# GRLV_DoubleRail_Part1_V0_1.net
KiCad netlist of a schematic drawn in Altium Designer
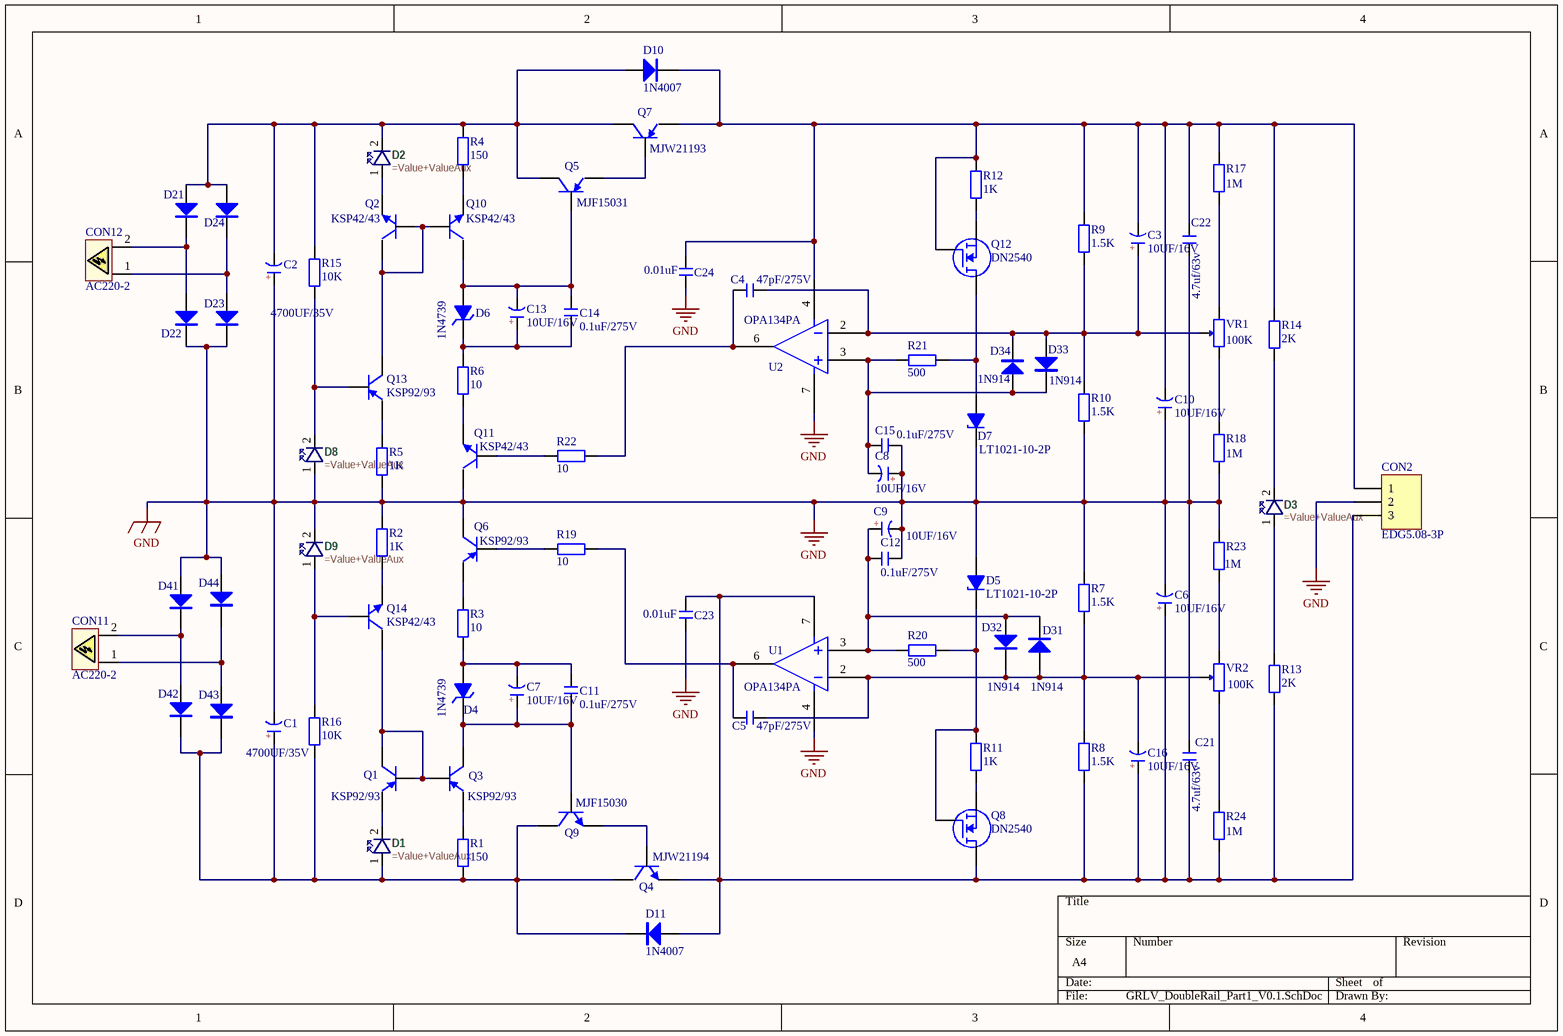
[diagram p0: GRLV_DoubleRail_Part1_V0.1.SchDoc]

(export (version "E")
  (design (tool "Eeschema 10.0.6"))
  (components
    (comp (ref "C1")
      (value "4700UF/35V")
      (footprint "CAP 11*35*60")
      (description "直插电解电容")
      (fields (field (name "版权归属") "源创客"))
      (libsource (lib "") (part "C-CAP_1"))
    )
    (comp (ref "C2")
      (value "4700UF/35V")
      (footprint "CAP 11*35*60")
      (description "直插电解电容")
      (fields (field (name "版权归属") "源创客"))
      (libsource (lib "") (part "C-CAP_1"))
    )
    (comp (ref "C3")
      (value "10UF/16V")
      (footprint "CAP 1.5*4*8")
      (description "直插电解电容")
      (fields (field (name "版权归属") "源创客"))
      (libsource (lib "") (part "C-CAP_1"))
    )
    (comp (ref "C4")
      (value "47pF/275V")
      (footprint "CBB 6.3*6.3*5")
      (description "CBB电容")
      (fields (field (name "版权归属") "源创客"))
      (libsource (lib "电阻-电容-电感") (part "C-CBB"))
    )
    (comp (ref "C5")
      (value "47pF/275V")
      (footprint "CBB 6.3*6.3*5")
      (description "CBB电容")
      (fields (field (name "版权归属") "源创客"))
      (libsource (lib "电阻-电容-电感") (part "C-CBB"))
    )
    (comp (ref "C6")
      (value "10UF/16V")
      (footprint "CAP 3.5*8*11.5")
      (description "直插电解电容")
      (fields (field (name "版权归属") "源创客"))
      (libsource (lib "") (part "C-CAP_1"))
    )
    (comp (ref "C7")
      (value "10UF/16V")
      (footprint "CAP 1.5*4*8")
      (description "直插电解电容")
      (fields (field (name "版权归属") "源创客"))
      (libsource (lib "") (part "C-CAP_1"))
    )
    (comp (ref "C8")
      (value "10UF/16V")
      (footprint "CAP 1.5*4*8")
      (description "直插电解电容")
      (fields (field (name "版权归属") "源创客"))
      (libsource (lib "电阻-电容-电感") (part "C-CAP"))
    )
    (comp (ref "C9")
      (value "10UF/16V")
      (footprint "CAP 1.5*4*8")
      (description "直插电解电容")
      (fields (field (name "版权归属") "源创客"))
      (libsource (lib "电阻-电容-电感") (part "C-CAP"))
    )
    (comp (ref "C10")
      (value "10UF/16V")
      (footprint "CAP 3.5*8*11.5")
      (description "直插电解电容")
      (fields (field (name "版权归属") "源创客"))
      (libsource (lib "") (part "C-CAP_1"))
    )
    (comp (ref "C11")
      (value "0.1uF/275V")
      (footprint "CBB 6.3*6.3*5")
      (description "CBB电容")
      (fields (field (name "版权归属") "源创客"))
      (libsource (lib "电阻-电容-电感") (part "C-CBB"))
    )
    (comp (ref "C12")
      (value "0.1uF/275V")
      (footprint "CBB 6.3*6.3*5")
      (description "CBB电容")
      (fields (field (name "版权归属") "源创客"))
      (libsource (lib "电阻-电容-电感") (part "C-CBB"))
    )
    (comp (ref "C13")
      (value "10UF/16V")
      (footprint "CAP 1.5*4*8")
      (description "直插电解电容")
      (fields (field (name "版权归属") "源创客"))
      (libsource (lib "") (part "C-CAP_1"))
    )
    (comp (ref "C14")
      (value "0.1uF/275V")
      (footprint "CBB 6.3*6.3*5")
      (description "CBB电容")
      (fields (field (name "版权归属") "源创客"))
      (libsource (lib "电阻-电容-电感") (part "C-CBB"))
    )
    (comp (ref "C15")
      (value "0.1uF/275V")
      (footprint "CBB 6.3*6.3*5")
      (description "CBB电容")
      (fields (field (name "版权归属") "源创客"))
      (libsource (lib "电阻-电容-电感") (part "C-CBB"))
    )
    (comp (ref "C16")
      (value "10UF/16V")
      (footprint "CAP 1.5*4*8")
      (description "直插电解电容")
      (fields (field (name "版权归属") "源创客"))
      (libsource (lib "") (part "C-CAP_1"))
    )
    (comp (ref "C21")
      (value "4.7uf/63v")
      (footprint "CBB 7.2*7.2*13")
      (description "MKS薄膜电容")
      (libsource (lib "电阻-电容-电感") (part "C-MKS"))
    )
    (comp (ref "C22")
      (value "4.7uf/63v")
      (footprint "CBB 7.2*7.2*13")
      (description "MKS薄膜电容")
      (libsource (lib "电阻-电容-电感") (part "C-MKS"))
    )
    (comp (ref "C23")
      (value "0.01uF")
      (footprint "CBB 6.3*6.3*5")
      (description "CBB电容")
      (fields (field (name "Comment") "0.01uF/275V") (field (name "版权归属") "源创客"))
      (libsource (lib "电阻-电容-电感") (part "C-CBB"))
    )
    (comp (ref "C24")
      (value "0.01uF")
      (footprint "CBB 6.3*6.3*5")
      (description "CBB电容")
      (fields (field (name "Comment") "0.01uF/275V") (field (name "版权归属") "源创客"))
      (libsource (lib "电阻-电容-电感") (part "C-CBB"))
    )
    (comp (ref "CON2")
      (value "EDG5.08-3P")
      (footprint "HX5.08-3S")
      (libsource (lib "Connectors") (part "EDG5.08-3P"))
    )
    (comp (ref "CON11")
      (value "AC220-2")
      (footprint "HX5.08-2S")
      (libsource (lib "Connectors") (part "AC220-2"))
    )
    (comp (ref "CON12")
      (value "AC220-2")
      (footprint "HX5.08-2S")
      (libsource (lib "Connectors") (part "AC220-2"))
    )
    (comp (ref "D1")
      (value "~")
      (footprint "LED 3MM-R")
      (description "直插式LED")
      (libsource (lib "LED") (part "LED"))
    )
    (comp (ref "D2")
      (value "~")
      (footprint "LED 3MM-R")
      (description "直插式LED")
      (libsource (lib "LED") (part "LED"))
    )
    (comp (ref "D3")
      (value "~")
      (footprint "LED 3MM-R")
      (description "直插式LED")
      (libsource (lib "LED") (part "LED"))
    )
    (comp (ref "D4")
      (value "1N4739")
      (footprint "DO-41")
      (description "9.1V/1W稳压管")
      (libsource (lib "二极管-整流桥") (part "1N4739"))
    )
    (comp (ref "D5")
      (value "LT1021-10-2P")
      (footprint "DIP8-300_MH")
      (description "10V Precision Reference 2 Pin Config")
      (libsource (lib "电压参考") (part "LT1021-10-2P"))
    )
    (comp (ref "D6")
      (value "1N4739")
      (footprint "DO-41")
      (description "9.1V/1W稳压管")
      (libsource (lib "二极管-整流桥") (part "1N4739"))
    )
    (comp (ref "D7")
      (value "LT1021-10-2P")
      (footprint "DIP8-300_MH")
      (description "10V Precision Reference 2 Pin Config")
      (libsource (lib "电压参考") (part "LT1021-10-2P"))
    )
    (comp (ref "D8")
      (value "~")
      (footprint "LED 3MM-R")
      (description "直插式LED")
      (libsource (lib "LED") (part "LED"))
    )
    (comp (ref "D9")
      (value "~")
      (footprint "LED 3MM-R")
      (description "直插式LED")
      (libsource (lib "LED") (part "LED"))
    )
    (comp (ref "D10")
      (value "1N4007")
      (footprint "DO-41")
      (description "整流二极管")
      (fields (field (name "版权归属") "源创客"))
      (libsource (lib "二极管-整流桥") (part "1N4007"))
    )
    (comp (ref "D11")
      (value "1N4007")
      (footprint "DO-41")
      (description "整流二极管")
      (fields (field (name "版权归属") "源创客"))
      (libsource (lib "二极管-整流桥") (part "1N4007"))
    )
    (comp (ref "D21")
      (value "VS-HFA08TB60-M3")
      (footprint "TO220AC")
      (description "Ultrafast Soft Recovery Diado 8A 600V")
      (libsource (lib "二极管-整流桥") (part "VS-HFA08TB60-M3"))
    )
    (comp (ref "D22")
      (value "VS-HFA08TB60-M3")
      (footprint "TO220AC")
      (description "Ultrafast Soft Recovery Diado 8A 600V")
      (libsource (lib "二极管-整流桥") (part "VS-HFA08TB60-M3"))
    )
    (comp (ref "D23")
      (value "VS-HFA08TB60-M3")
      (footprint "TO220AC")
      (description "Ultrafast Soft Recovery Diado 8A 600V")
      (libsource (lib "二极管-整流桥") (part "VS-HFA08TB60-M3"))
    )
    (comp (ref "D24")
      (value "VS-HFA08TB60-M3")
      (footprint "TO220AC")
      (description "Ultrafast Soft Recovery Diado 8A 600V")
      (libsource (lib "二极管-整流桥") (part "VS-HFA08TB60-M3"))
    )
    (comp (ref "D31")
      (value "1N914")
      (footprint "DO-35")
      (description "高速开关管 1V/0.25W")
      (libsource (lib "二极管-整流桥") (part "1N914"))
    )
    (comp (ref "D32")
      (value "1N914")
      (footprint "DO-35")
      (description "高速开关管 1V/0.25W")
      (libsource (lib "二极管-整流桥") (part "1N914"))
    )
    (comp (ref "D33")
      (value "1N914")
      (footprint "DO-35")
      (description "高速开关管 1V/0.25W")
      (libsource (lib "二极管-整流桥") (part "1N914"))
    )
    (comp (ref "D34")
      (value "1N914")
      (footprint "DO-35")
      (description "高速开关管 1V/0.25W")
      (libsource (lib "二极管-整流桥") (part "1N914"))
    )
    (comp (ref "D41")
      (value "VS-HFA08TB60-M3")
      (footprint "TO220AC")
      (description "Ultrafast Soft Recovery Diado 8A 600V")
      (libsource (lib "二极管-整流桥") (part "VS-HFA08TB60-M3"))
    )
    (comp (ref "D42")
      (value "VS-HFA08TB60-M3")
      (footprint "TO220AC")
      (description "Ultrafast Soft Recovery Diado 8A 600V")
      (libsource (lib "二极管-整流桥") (part "VS-HFA08TB60-M3"))
    )
    (comp (ref "D43")
      (value "VS-HFA08TB60-M3")
      (footprint "TO220AC")
      (description "Ultrafast Soft Recovery Diado 8A 600V")
      (libsource (lib "二极管-整流桥") (part "VS-HFA08TB60-M3"))
    )
    (comp (ref "D44")
      (value "VS-HFA08TB60-M3")
      (footprint "TO220AC")
      (description "Ultrafast Soft Recovery Diado 8A 600V")
      (libsource (lib "二极管-整流桥") (part "VS-HFA08TB60-M3"))
    )
    (comp (ref "Q1")
      (value "KSP92/93")
      (footprint "TO92A")
      (description "High Voltage PNP Transistor")
      (libsource (lib "三极管") (part "KSP92/93"))
    )
    (comp (ref "Q2")
      (value "KSP42/43")
      (footprint "TO92A")
      (description "High Voltage NPN Transistor")
      (libsource (lib "三极管") (part "KSP42/43"))
    )
    (comp (ref "Q3")
      (value "KSP92/93")
      (footprint "TO92A")
      (description "High Voltage PNP Transistor")
      (libsource (lib "三极管") (part "KSP92/93"))
    )
    (comp (ref "Q4")
      (value "MJW21194")
      (footprint "TO247V")
      (description "Power NPN Transistor")
      (libsource (lib "三极管") (part "MJW21194"))
    )
    (comp (ref "Q5")
      (value "MJF15031")
      (footprint "TO220V")
      (description "Power PNP Transistor")
      (libsource (lib "三极管") (part "MJF15031"))
    )
    (comp (ref "Q6")
      (value "KSP92/93")
      (footprint "TO92A")
      (description "High Voltage PNP Transistor")
      (libsource (lib "三极管") (part "KSP92/93"))
    )
    (comp (ref "Q7")
      (value "MJW21193")
      (footprint "TO247V")
      (description "Power PNP Transistor")
      (libsource (lib "三极管") (part "MJW21193"))
    )
    (comp (ref "Q8")
      (value "DN2540")
      (footprint "TO92A")
      (description "N沟道耗尽型DMOS场效应管 400V/150ma")
      (libsource (lib "场效应管") (part "DN2540"))
    )
    (comp (ref "Q9")
      (value "MJF15030")
      (footprint "TO220V")
      (description "Power NPN Transistor")
      (libsource (lib "三极管") (part "MJF15030"))
    )
    (comp (ref "Q10")
      (value "KSP42/43")
      (footprint "TO92A")
      (description "High Voltage NPN Transistor")
      (libsource (lib "三极管") (part "KSP42/43"))
    )
    (comp (ref "Q11")
      (value "KSP42/43")
      (footprint "TO92A")
      (description "High Voltage NPN Transistor")
      (libsource (lib "三极管") (part "KSP42/43"))
    )
    (comp (ref "Q12")
      (value "DN2540")
      (footprint "TO92A")
      (description "N沟道耗尽型DMOS场效应管 400V/150ma")
      (libsource (lib "场效应管") (part "DN2540"))
    )
    (comp (ref "Q13")
      (value "KSP92/93")
      (footprint "TO92A")
      (description "High Voltage PNP Transistor")
      (libsource (lib "三极管") (part "KSP92/93"))
    )
    (comp (ref "Q14")
      (value "KSP42/43")
      (footprint "TO92A")
      (description "High Voltage NPN Transistor")
      (libsource (lib "三极管") (part "KSP42/43"))
    )
    (comp (ref "R1")
      (value "150")
      (footprint "RS 1/4W")
      (description "直插色环电阻")
      (fields (field (name "版权归属") "源创客"))
      (libsource (lib "电阻-电容-电感") (part "R-CRR"))
    )
    (comp (ref "R2")
      (value "1K")
      (footprint "RS 1/4W")
      (description "直插色环电阻")
      (fields (field (name "版权归属") "源创客"))
      (libsource (lib "电阻-电容-电感") (part "R-CRR"))
    )
    (comp (ref "R3")
      (value "10")
      (footprint "RS 1/4W")
      (description "直插色环电阻")
      (fields (field (name "版权归属") "源创客"))
      (libsource (lib "电阻-电容-电感") (part "R-CRR"))
    )
    (comp (ref "R4")
      (value "150")
      (footprint "RS 1/4W")
      (description "直插色环电阻")
      (fields (field (name "版权归属") "源创客"))
      (libsource (lib "电阻-电容-电感") (part "R-CRR"))
    )
    (comp (ref "R5")
      (value "1K")
      (footprint "RS 1/4W")
      (description "直插色环电阻")
      (fields (field (name "版权归属") "源创客"))
      (libsource (lib "电阻-电容-电感") (part "R-CRR"))
    )
    (comp (ref "R6")
      (value "10")
      (footprint "RS 1/4W")
      (description "直插色环电阻")
      (fields (field (name "版权归属") "源创客"))
      (libsource (lib "电阻-电容-电感") (part "R-CRR"))
    )
    (comp (ref "R7")
      (value "1.5K")
      (footprint "RS 1/4W")
      (description "直插色环电阻")
      (fields (field (name "版权归属") "源创客"))
      (libsource (lib "电阻-电容-电感") (part "R-CRR"))
    )
    (comp (ref "R8")
      (value "1.5K")
      (footprint "RS 1/4W")
      (description "直插色环电阻")
      (fields (field (name "版权归属") "源创客"))
      (libsource (lib "电阻-电容-电感") (part "R-CRR"))
    )
    (comp (ref "R9")
      (value "1.5K")
      (footprint "RS 1/4W")
      (description "直插色环电阻")
      (fields (field (name "版权归属") "源创客"))
      (libsource (lib "电阻-电容-电感") (part "R-CRR"))
    )
    (comp (ref "R10")
      (value "1.5K")
      (footprint "RS 1/4W")
      (description "直插色环电阻")
      (fields (field (name "版权归属") "源创客"))
      (libsource (lib "电阻-电容-电感") (part "R-CRR"))
    )
    (comp (ref "R11")
      (value "1K")
      (footprint "RS 1/4W")
      (description "直插色环电阻")
      (fields (field (name "版权归属") "源创客"))
      (libsource (lib "电阻-电容-电感") (part "R-CRR"))
    )
    (comp (ref "R12")
      (value "1K")
      (footprint "RS 1/4W")
      (description "直插色环电阻")
      (fields (field (name "版权归属") "源创客"))
      (libsource (lib "电阻-电容-电感") (part "R-CRR"))
    )
    (comp (ref "R13")
      (value "2K")
      (footprint "RS 1/4W")
      (description "直插色环电阻")
      (fields (field (name "版权归属") "源创客"))
      (libsource (lib "电阻-电容-电感") (part "R-CRR"))
    )
    (comp (ref "R14")
      (value "2K")
      (footprint "RS 1/4W")
      (description "直插色环电阻")
      (fields (field (name "版权归属") "源创客"))
      (libsource (lib "电阻-电容-电感") (part "R-CRR"))
    )
    (comp (ref "R15")
      (value "10K")
      (footprint "RS 1/4W")
      (description "直插色环电阻")
      (fields (field (name "版权归属") "源创客"))
      (libsource (lib "电阻-电容-电感") (part "R-CRR"))
    )
    (comp (ref "R16")
      (value "10K")
      (footprint "RS 1/4W")
      (description "直插色环电阻")
      (fields (field (name "版权归属") "源创客"))
      (libsource (lib "电阻-电容-电感") (part "R-CRR"))
    )
    (comp (ref "R17")
      (value "1M")
      (footprint "RS 1/4W")
      (description "直插色环电阻")
      (fields (field (name "版权归属") "源创客"))
      (libsource (lib "电阻-电容-电感") (part "R-CRR"))
    )
    (comp (ref "R18")
      (value "1M")
      (footprint "RS 1/4W")
      (description "直插色环电阻")
      (fields (field (name "版权归属") "源创客"))
      (libsource (lib "电阻-电容-电感") (part "R-CRR"))
    )
    (comp (ref "R19")
      (value "10")
      (footprint "RS 1/4W")
      (description "直插色环电阻")
      (fields (field (name "版权归属") "源创客"))
      (libsource (lib "电阻-电容-电感") (part "R-CRR"))
    )
    (comp (ref "R20")
      (value "500")
      (footprint "RS 1/4W")
      (description "直插色环电阻")
      (fields (field (name "版权归属") "源创客"))
      (libsource (lib "电阻-电容-电感") (part "R-CRR"))
    )
    (comp (ref "R21")
      (value "500")
      (footprint "RS 1/4W")
      (description "直插色环电阻")
      (fields (field (name "版权归属") "源创客"))
      (libsource (lib "电阻-电容-电感") (part "R-CRR"))
    )
    (comp (ref "R22")
      (value "10")
      (footprint "RS 1/4W")
      (description "直插色环电阻")
      (fields (field (name "版权归属") "源创客"))
      (libsource (lib "电阻-电容-电感") (part "R-CRR"))
    )
    (comp (ref "R23")
      (value "1M")
      (footprint "RS 1/4W")
      (description "直插色环电阻")
      (fields (field (name "版权归属") "源创客"))
      (libsource (lib "电阻-电容-电感") (part "R-CRR"))
    )
    (comp (ref "R24")
      (value "1M")
      (footprint "RS 1/4W")
      (description "直插色环电阻")
      (fields (field (name "版权归属") "源创客"))
      (libsource (lib "电阻-电容-电感") (part "R-CRR"))
    )
    (comp (ref "U1") (value "OPA134PA") (footprint "DIP8-300_MH") (libsource (lib "运放") (part "OPA134PA")))
    (comp (ref "U2") (value "OPA134PA") (footprint "DIP8-300_MH") (libsource (lib "运放") (part "OPA134PA")))
    (comp (ref "VR1")
      (value "100K")
      (footprint "RS 1/2W-VR")
      (description "直插可调电阻-顶调")
      (fields (field (name "Comment") "VR-W"))
      (libsource (lib "电阻-电容-电感") (part "VR-W"))
    )
    (comp (ref "VR2")
      (value "100K")
      (footprint "RS 1/2W-VR")
      (description "直插可调电阻-顶调")
      (fields (field (name "Comment") "VR-W"))
      (libsource (lib "电阻-电容-电感") (part "VR-W"))
    )
  )
  (nets
    (net (code "1") (name "GND") (class "Default")
      (node (ref "C1") (pin "2") (pinfunction "K_2") (pintype "passive"))
      (node (ref "C10") (pin "1") (pinfunction "A_1") (pintype "passive"))
      (node (ref "C12") (pin "2") (pinfunction "2_2") (pintype "passive"))
      (node (ref "C15") (pin "2") (pinfunction "2_2") (pintype "passive"))
      (node (ref "C2") (pin "1") (pinfunction "A_1") (pintype "passive"))
      (node (ref "C21") (pin "2") (pinfunction "2_2") (pintype "passive"))
      (node (ref "C22") (pin "1") (pinfunction "1_1") (pintype "passive"))
      (node (ref "C23") (pin "1") (pinfunction "1_1") (pintype "passive"))
      (node (ref "C24") (pin "1") (pinfunction "1_1") (pintype "passive"))
      (node (ref "C6") (pin "2") (pinfunction "K_2") (pintype "passive"))
      (node (ref "C8") (pin "1") (pinfunction "A_1") (pintype "passive"))
      (node (ref "C9") (pin "2") (pinfunction "K_2") (pintype "passive"))
      (node (ref "CON2") (pin "2") (pinfunction "2_2") (pintype "passive"))
      (node (ref "D22") (pin "1") (pinfunction "Cathode_1") (pintype "passive"))
      (node (ref "D23") (pin "1") (pinfunction "Cathode_1") (pintype "passive"))
      (node (ref "D41") (pin "2") (pinfunction "Anode_2") (pintype "passive"))
      (node (ref "D44") (pin "2") (pinfunction "Anode_2") (pintype "passive"))
      (node (ref "D5") (pin "4") (pinfunction "A_4") (pintype "passive"))
      (node (ref "D7") (pin "6") (pinfunction "K_6") (pintype "passive"))
      (node (ref "D8") (pin "1") (pinfunction "A_1") (pintype "passive"))
      (node (ref "D9") (pin "2") (pinfunction "K_2") (pintype "passive"))
      (node (ref "Q11") (pin "3") (pinfunction "C_3") (pintype "passive"))
      (node (ref "Q6") (pin "3") (pinfunction "C_3") (pintype "passive"))
      (node (ref "R10") (pin "1") (pinfunction "1_1") (pintype "passive"))
      (node (ref "R18") (pin "1") (pinfunction "1_1") (pintype "passive"))
      (node (ref "R2") (pin "2") (pinfunction "2_2") (pintype "passive"))
      (node (ref "R23") (pin "2") (pinfunction "2_2") (pintype "passive"))
      (node (ref "R5") (pin "1") (pinfunction "1_1") (pintype "passive"))
      (node (ref "R7") (pin "2") (pinfunction "2_2") (pintype "passive"))
      (node (ref "U1") (pin "4") (pinfunction "V-_4") (pintype "passive"))
      (node (ref "U2") (pin "7") (pinfunction "V+_7") (pintype "passive"))
    )
    (net (code "2") (name "Net-(C1-A)") (class "Default")
      (node (ref "C1") (pin "1") (pinfunction "A_1") (pintype "passive"))
      (node (ref "D1") (pin "1") (pinfunction "A_1") (pintype "passive"))
      (node (ref "D11") (pin "2") (pinfunction "K_2") (pintype "passive"))
      (node (ref "D42") (pin "1") (pinfunction "Cathode_1") (pintype "passive"))
      (node (ref "D43") (pin "1") (pinfunction "Cathode_1") (pintype "passive"))
      (node (ref "Q4") (pin "2") (pinfunction "C_2") (pintype "passive"))
      (node (ref "Q9") (pin "2") (pinfunction "C_2") (pintype "passive"))
      (node (ref "R1") (pin "1") (pinfunction "1_1") (pintype "passive"))
      (node (ref "R16") (pin "1") (pinfunction "1_1") (pintype "passive"))
    )
    (net (code "3") (name "Net-(C2-K)") (class "Default")
      (node (ref "C2") (pin "2") (pinfunction "K_2") (pintype "passive"))
      (node (ref "D10") (pin "1") (pinfunction "A_1") (pintype "passive"))
      (node (ref "D2") (pin "2") (pinfunction "K_2") (pintype "passive"))
      (node (ref "D21") (pin "2") (pinfunction "Anode_2") (pintype "passive"))
      (node (ref "D24") (pin "2") (pinfunction "Anode_2") (pintype "passive"))
      (node (ref "Q5") (pin "2") (pinfunction "C_2") (pintype "passive"))
      (node (ref "Q7") (pin "2") (pinfunction "C_2") (pintype "passive"))
      (node (ref "R15") (pin "2") (pinfunction "2_2") (pintype "passive"))
      (node (ref "R4") (pin "2") (pinfunction "2_2") (pintype "passive"))
    )
    (net (code "4") (name "Net-(C3-A)") (class "Default")
      (node (ref "C3") (pin "1") (pinfunction "A_1") (pintype "passive"))
      (node (ref "C4") (pin "2") (pinfunction "2_2") (pintype "passive"))
      (node (ref "D33") (pin "1") (pinfunction "A_1") (pintype "passive"))
      (node (ref "D34") (pin "2") (pinfunction "K_2") (pintype "passive"))
      (node (ref "R10") (pin "2") (pinfunction "2_2") (pintype "passive"))
      (node (ref "R9") (pin "1") (pinfunction "1_1") (pintype "passive"))
      (node (ref "U2") (pin "2") (pinfunction "-in_2") (pintype "passive"))
      (node (ref "VR1") (pin "3") (pinfunction "3_3") (pintype "passive"))
    )
    (net (code "5") (name "Net-(C7-A)") (class "Default")
      (node (ref "C11") (pin "1") (pinfunction "1_1") (pintype "passive"))
      (node (ref "C7") (pin "1") (pinfunction "A_1") (pintype "passive"))
      (node (ref "D4") (pin "2") (pinfunction "K_2") (pintype "passive"))
      (node (ref "Q3") (pin "3") (pinfunction "C_3") (pintype "passive"))
      (node (ref "Q9") (pin "1") (pinfunction "B_1") (pintype "passive"))
    )
    (net (code "6") (name "Net-(C7-K)") (class "Default")
      (node (ref "C11") (pin "2") (pinfunction "2_2") (pintype "passive"))
      (node (ref "C7") (pin "2") (pinfunction "K_2") (pintype "passive"))
      (node (ref "D4") (pin "1") (pinfunction "A_1") (pintype "passive"))
      (node (ref "R3") (pin "1") (pinfunction "1_1") (pintype "passive"))
    )
    (net (code "7") (name "Net-(C8-K)") (class "Default")
      (node (ref "C15") (pin "1") (pinfunction "1_1") (pintype "passive"))
      (node (ref "C8") (pin "2") (pinfunction "K_2") (pintype "passive"))
      (node (ref "D33") (pin "2") (pinfunction "K_2") (pintype "passive"))
      (node (ref "D34") (pin "1") (pinfunction "A_1") (pintype "passive"))
      (node (ref "R21") (pin "1") (pinfunction "1_1") (pintype "passive"))
      (node (ref "U2") (pin "3") (pinfunction "+in_3") (pintype "passive"))
    )
    (net (code "8") (name "Net-(C9-A)") (class "Default")
      (node (ref "C12") (pin "1") (pinfunction "1_1") (pintype "passive"))
      (node (ref "C9") (pin "1") (pinfunction "A_1") (pintype "passive"))
      (node (ref "D31") (pin "2") (pinfunction "K_2") (pintype "passive"))
      (node (ref "D32") (pin "1") (pinfunction "A_1") (pintype "passive"))
      (node (ref "R20") (pin "1") (pinfunction "1_1") (pintype "passive"))
      (node (ref "U1") (pin "3") (pinfunction "+in_3") (pintype "passive"))
    )
    (net (code "9") (name "Net-(C10-K)") (class "Default")
      (node (ref "C10") (pin "2") (pinfunction "K_2") (pintype "passive"))
      (node (ref "C22") (pin "2") (pinfunction "2_2") (pintype "passive"))
      (node (ref "C24") (pin "2") (pinfunction "2_2") (pintype "passive"))
      (node (ref "C3") (pin "2") (pinfunction "K_2") (pintype "passive"))
      (node (ref "CON2") (pin "1") (pinfunction "1_1") (pintype "passive"))
      (node (ref "D10") (pin "2") (pinfunction "K_2") (pintype "passive"))
      (node (ref "Q12") (pin "2") (pinfunction "G_2") (pintype "passive"))
      (node (ref "Q7") (pin "3") (pinfunction "E_3") (pintype "passive"))
      (node (ref "R12") (pin "2") (pinfunction "2_2") (pintype "passive"))
      (node (ref "R14") (pin "2") (pinfunction "2_2") (pintype "passive"))
      (node (ref "R17") (pin "2") (pinfunction "2_2") (pintype "passive"))
      (node (ref "R9") (pin "2") (pinfunction "2_2") (pintype "passive"))
      (node (ref "U2") (pin "4") (pinfunction "V-_4") (pintype "passive"))
    )
    (net (code "10") (name "Net-(C13-A)") (class "Default")
      (node (ref "C13") (pin "1") (pinfunction "A_1") (pintype "passive"))
      (node (ref "C14") (pin "1") (pinfunction "1_1") (pintype "passive"))
      (node (ref "D6") (pin "2") (pinfunction "K_2") (pintype "passive"))
      (node (ref "R6") (pin "2") (pinfunction "2_2") (pintype "passive"))
    )
    (net (code "11") (name "Net-(C13-K)") (class "Default")
      (node (ref "C13") (pin "2") (pinfunction "K_2") (pintype "passive"))
      (node (ref "C14") (pin "2") (pinfunction "2_2") (pintype "passive"))
      (node (ref "D6") (pin "1") (pinfunction "A_1") (pintype "passive"))
      (node (ref "Q10") (pin "3") (pinfunction "C_3") (pintype "passive"))
      (node (ref "Q5") (pin "1") (pinfunction "B_1") (pintype "passive"))
    )
    (net (code "12") (name "Net-(C16-A)") (class "Default")
      (node (ref "C16") (pin "1") (pinfunction "A_1") (pintype "passive"))
      (node (ref "C21") (pin "1") (pinfunction "1_1") (pintype "passive"))
      (node (ref "C23") (pin "2") (pinfunction "2_2") (pintype "passive"))
      (node (ref "C6") (pin "1") (pinfunction "A_1") (pintype "passive"))
      (node (ref "CON2") (pin "3") (pinfunction "3_3") (pintype "passive"))
      (node (ref "D11") (pin "1") (pinfunction "A_1") (pintype "passive"))
      (node (ref "Q4") (pin "3") (pinfunction "E_3") (pintype "passive"))
      (node (ref "Q8") (pin "3") (pinfunction "D_3") (pintype "passive"))
      (node (ref "R13") (pin "2") (pinfunction "2_2") (pintype "passive"))
      (node (ref "R24") (pin "1") (pinfunction "1_1") (pintype "passive"))
      (node (ref "R8") (pin "1") (pinfunction "1_1") (pintype "passive"))
      (node (ref "U1") (pin "7") (pinfunction "V+_7") (pintype "passive"))
    )
    (net (code "13") (name "Net-(C16-K)") (class "Default")
      (node (ref "C16") (pin "2") (pinfunction "K_2") (pintype "passive"))
      (node (ref "C5") (pin "2") (pinfunction "2_2") (pintype "passive"))
      (node (ref "D31") (pin "1") (pinfunction "A_1") (pintype "passive"))
      (node (ref "D32") (pin "2") (pinfunction "K_2") (pintype "passive"))
      (node (ref "R7") (pin "1") (pinfunction "1_1") (pintype "passive"))
      (node (ref "R8") (pin "2") (pinfunction "2_2") (pintype "passive"))
      (node (ref "U1") (pin "2") (pinfunction "-in_2") (pintype "passive"))
      (node (ref "VR2") (pin "3") (pinfunction "3_3") (pintype "passive"))
    )
    (net (code "14") (name "Net-(CON11-G)") (class "Default")
      (node (ref "CON11") (pin "2") (pinfunction "G_2") (pintype "passive"))
      (node (ref "D41") (pin "1") (pinfunction "Cathode_1") (pintype "passive"))
      (node (ref "D42") (pin "2") (pinfunction "Anode_2") (pintype "passive"))
    )
    (net (code "15") (name "Net-(CON11-L)") (class "Default")
      (node (ref "CON11") (pin "1") (pinfunction "L_1") (pintype "passive"))
      (node (ref "D43") (pin "2") (pinfunction "Anode_2") (pintype "passive"))
      (node (ref "D44") (pin "1") (pinfunction "Cathode_1") (pintype "passive"))
    )
    (net (code "16") (name "Net-(CON12-G)") (class "Default")
      (node (ref "CON12") (pin "2") (pinfunction "G_2") (pintype "passive"))
      (node (ref "D21") (pin "1") (pinfunction "Cathode_1") (pintype "passive"))
      (node (ref "D22") (pin "2") (pinfunction "Anode_2") (pintype "passive"))
    )
    (net (code "17") (name "Net-(CON12-L)") (class "Default")
      (node (ref "CON12") (pin "1") (pinfunction "L_1") (pintype "passive"))
      (node (ref "D23") (pin "2") (pinfunction "Anode_2") (pintype "passive"))
      (node (ref "D24") (pin "1") (pinfunction "Cathode_1") (pintype "passive"))
    )
    (net (code "18") (name "Net-(D1-K)") (class "Default")
      (node (ref "D1") (pin "2") (pinfunction "K_2") (pintype "passive"))
      (node (ref "Q1") (pin "1") (pinfunction "E_1") (pintype "passive"))
    )
    (net (code "19") (name "Net-(D2-A)") (class "Default")
      (node (ref "D2") (pin "1") (pinfunction "A_1") (pintype "passive"))
      (node (ref "Q2") (pin "1") (pinfunction "E_1") (pintype "passive"))
    )
    (net (code "20") (name "Net-(D3-A)") (class "Default")
      (node (ref "D3") (pin "1") (pinfunction "A_1") (pintype "passive"))
      (node (ref "R13") (pin "1") (pinfunction "1_1") (pintype "passive"))
    )
    (net (code "21") (name "Net-(D3-K)") (class "Default")
      (node (ref "D3") (pin "2") (pinfunction "K_2") (pintype "passive"))
      (node (ref "R14") (pin "1") (pinfunction "1_1") (pintype "passive"))
    )
    (net (code "22") (name "Net-(D5-K)") (class "Default")
      (node (ref "D5") (pin "6") (pinfunction "K_6") (pintype "passive"))
      (node (ref "Q8") (pin "2") (pinfunction "G_2") (pintype "passive"))
      (node (ref "R11") (pin "2") (pinfunction "2_2") (pintype "passive"))
      (node (ref "R20") (pin "2") (pinfunction "2_2") (pintype "passive"))
    )
    (net (code "23") (name "Net-(D7-A)") (class "Default")
      (node (ref "D7") (pin "4") (pinfunction "A_4") (pintype "passive"))
      (node (ref "Q12") (pin "3") (pinfunction "D_3") (pintype "passive"))
      (node (ref "R21") (pin "2") (pinfunction "2_2") (pintype "passive"))
    )
    (net (code "24") (name "Net-(D8-K)") (class "Default")
      (node (ref "D8") (pin "2") (pinfunction "K_2") (pintype "passive"))
      (node (ref "Q13") (pin "2") (pinfunction "B_2") (pintype "passive"))
      (node (ref "R15") (pin "1") (pinfunction "1_1") (pintype "passive"))
    )
    (net (code "25") (name "Net-(D9-A)") (class "Default")
      (node (ref "D9") (pin "1") (pinfunction "A_1") (pintype "passive"))
      (node (ref "Q14") (pin "2") (pinfunction "B_2") (pintype "passive"))
      (node (ref "R16") (pin "2") (pinfunction "2_2") (pintype "passive"))
    )
    (net (code "26") (name "Net-(Q1-B)") (class "Default")
      (node (ref "Q1") (pin "2") (pinfunction "B_2") (pintype "passive"))
      (node (ref "Q1") (pin "3") (pinfunction "C_3") (pintype "passive"))
      (node (ref "Q14") (pin "3") (pinfunction "C_3") (pintype "passive"))
      (node (ref "Q3") (pin "2") (pinfunction "B_2") (pintype "passive"))
    )
    (net (code "27") (name "Net-(Q3-E)") (class "Default")
      (node (ref "Q3") (pin "1") (pinfunction "E_1") (pintype "passive"))
      (node (ref "R1") (pin "2") (pinfunction "2_2") (pintype "passive"))
    )
    (net (code "28") (name "Net-(Q4-B)") (class "Default")
      (node (ref "Q4") (pin "1") (pinfunction "B_1") (pintype "passive"))
      (node (ref "Q9") (pin "3") (pinfunction "E_3") (pintype "passive"))
    )
    (net (code "29") (name "Net-(Q5-E)") (class "Default")
      (node (ref "Q5") (pin "3") (pinfunction "E_3") (pintype "passive"))
      (node (ref "Q7") (pin "1") (pinfunction "B_1") (pintype "passive"))
    )
    (net (code "30") (name "Net-(Q6-B)") (class "Default")
      (node (ref "Q6") (pin "2") (pinfunction "B_2") (pintype "passive"))
      (node (ref "R19") (pin "1") (pinfunction "1_1") (pintype "passive"))
    )
    (net (code "31") (name "Net-(Q6-E)") (class "Default")
      (node (ref "Q6") (pin "1") (pinfunction "E_1") (pintype "passive"))
      (node (ref "R3") (pin "2") (pinfunction "2_2") (pintype "passive"))
    )
    (net (code "32") (name "Net-(Q8-S)") (class "Default")
      (node (ref "Q8") (pin "1") (pinfunction "S_1") (pintype "passive"))
      (node (ref "R11") (pin "1") (pinfunction "1_1") (pintype "passive"))
    )
    (net (code "33") (name "Net-(Q10-B)") (class "Default")
      (node (ref "Q10") (pin "2") (pinfunction "B_2") (pintype "passive"))
      (node (ref "Q13") (pin "3") (pinfunction "C_3") (pintype "passive"))
      (node (ref "Q2") (pin "2") (pinfunction "B_2") (pintype "passive"))
      (node (ref "Q2") (pin "3") (pinfunction "C_3") (pintype "passive"))
    )
    (net (code "34") (name "Net-(Q10-E)") (class "Default")
      (node (ref "Q10") (pin "1") (pinfunction "E_1") (pintype "passive"))
      (node (ref "R4") (pin "1") (pinfunction "1_1") (pintype "passive"))
    )
    (net (code "35") (name "Net-(Q11-B)") (class "Default")
      (node (ref "Q11") (pin "2") (pinfunction "B_2") (pintype "passive"))
      (node (ref "R22") (pin "1") (pinfunction "1_1") (pintype "passive"))
    )
    (net (code "36") (name "Net-(Q11-E)") (class "Default")
      (node (ref "Q11") (pin "1") (pinfunction "E_1") (pintype "passive"))
      (node (ref "R6") (pin "1") (pinfunction "1_1") (pintype "passive"))
    )
    (net (code "37") (name "Net-(Q12-S)") (class "Default")
      (node (ref "Q12") (pin "1") (pinfunction "S_1") (pintype "passive"))
      (node (ref "R12") (pin "1") (pinfunction "1_1") (pintype "passive"))
    )
    (net (code "38") (name "Net-(Q13-E)") (class "Default")
      (node (ref "Q13") (pin "1") (pinfunction "E_1") (pintype "passive"))
      (node (ref "R5") (pin "2") (pinfunction "2_2") (pintype "passive"))
    )
    (net (code "39") (name "Net-(Q14-E)") (class "Default")
      (node (ref "Q14") (pin "1") (pinfunction "E_1") (pintype "passive"))
      (node (ref "R2") (pin "1") (pinfunction "1_1") (pintype "passive"))
    )
    (net (code "40") (name "Net-(R17-Pad1)") (class "Default")
      (node (ref "R17") (pin "1") (pinfunction "1_1") (pintype "passive"))
      (node (ref "VR1") (pin "2") (pinfunction "2_2") (pintype "passive"))
    )
    (net (code "41") (name "Net-(R18-Pad2)") (class "Default")
      (node (ref "R18") (pin "2") (pinfunction "2_2") (pintype "passive"))
      (node (ref "VR1") (pin "1") (pinfunction "1_1") (pintype "passive"))
    )
    (net (code "42") (name "Net-(R23-Pad1)") (class "Default")
      (node (ref "R23") (pin "1") (pinfunction "1_1") (pintype "passive"))
      (node (ref "VR2") (pin "2") (pinfunction "2_2") (pintype "passive"))
    )
    (net (code "43") (name "Net-(R24-Pad2)") (class "Default")
      (node (ref "R24") (pin "2") (pinfunction "2_2") (pintype "passive"))
      (node (ref "VR2") (pin "1") (pinfunction "1_1") (pintype "passive"))
    )
    (net (code "44") (name "Net-(U1-out)") (class "Default")
      (node (ref "C5") (pin "1") (pinfunction "1_1") (pintype "passive"))
      (node (ref "R19") (pin "2") (pinfunction "2_2") (pintype "passive"))
      (node (ref "U1") (pin "6") (pinfunction "out_6") (pintype "passive"))
    )
    (net (code "45") (name "Net-(U2-out)") (class "Default")
      (node (ref "C4") (pin "1") (pinfunction "1_1") (pintype "passive"))
      (node (ref "R22") (pin "2") (pinfunction "2_2") (pintype "passive"))
      (node (ref "U2") (pin "6") (pinfunction "out_6") (pintype "passive"))
    )
  )
)
